# power.net
KiCad netlist of a schematic drawn in Altium Designer
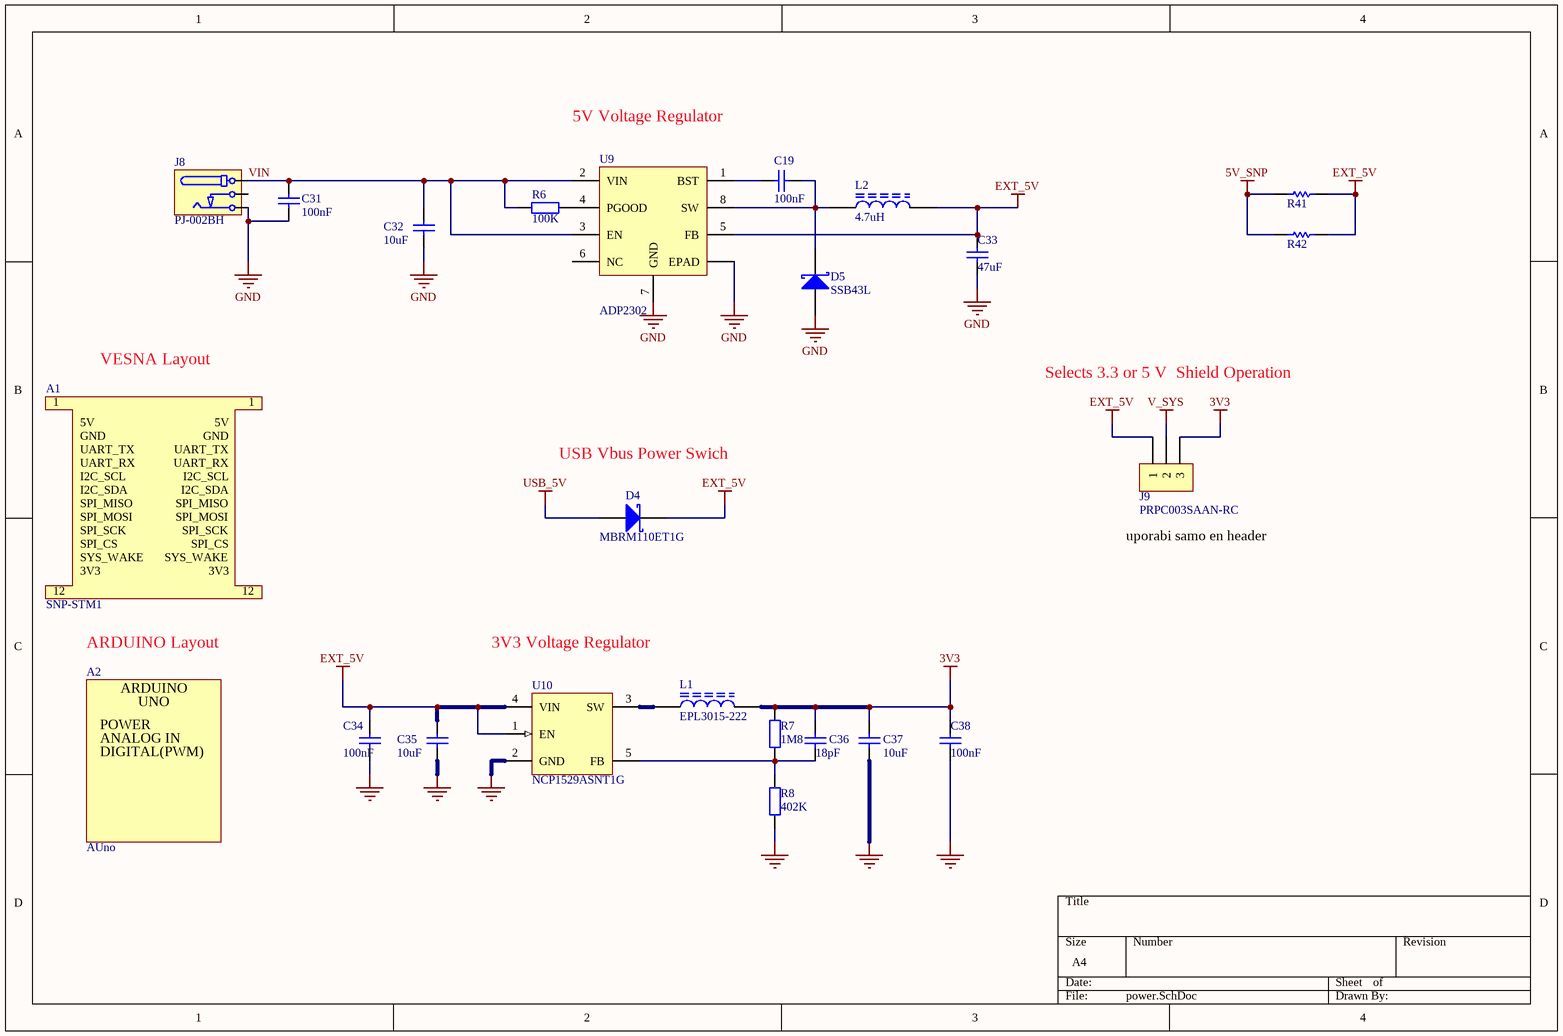
[diagram p0: power.SchDoc]

(export (version "E")
  (design (tool "Eeschema 10.0.6"))
  (components
    (comp (ref "A1")
      (value "SNP-STM1")
      (footprint "SNP-STM1")
      (description "SNP-STM1 Vesna Processor Module, Mechanical PCB Components without Connectors")
      (libsource (lib "SNP-STM1") (part "SNP-STM1"))
    )
    (comp (ref "A2") (value "AUno") (footprint "PCBComponent_1") (libsource (lib "AUNOLayout") (part "AUno")))
    (comp (ref "C19")
      (value "100nF")
      (footprint "CAPC0402(1005)60_L")
      (description "CAP 100nF 10V ±5% 0402 (1005 Metric) Thickness 0.6mm SMD")
      (fields (field (name "TOLERANCE") "Â±5%") (field (name "Comment") "CAP 100nF 10V 0402(1005)"))
      (libsource (lib "Altium Content Vault") (part "CMP-1034-02064-1"))
    )
    (comp (ref "C31")
      (value "100nF")
      (footprint "CAPC0402(1005)60_M")
      (description "CAP 100nF 50V ±10% 0402 (1005 Metric) Thickness 0.6mm SMD")
      (fields (field (name "TOLERANCE") "±10%") (field (name "Comment") "CAP 100nF 50V 0402(1005)"))
      (libsource (lib "Altium Content Vault") (part "CMP-1034-02077-1"))
    )
    (comp (ref "C32")
      (value "10uF")
      (footprint "CAPC0805(2012)145_N")
      (description "CAP 10uF 10V ±20% 0805 (2012 Metric) Thickness 1.45mm SMD")
      (fields (field (name "TOLERANCE") "±20%"))
      (libsource (lib "Altium Content Vault") (part "CMP-1036-04924-1"))
    )
    (comp (ref "C33")
      (value "47uF")
      (footprint "CAPC0402(1005)60_M")
      (description "CAP 100nF 50V ±10% 0402 (1005 Metric) Thickness 0.6mm SMD")
      (fields (field (name "TOLERANCE") "±10%") (field (name "Comment") "CAP 100nF 50V 0402(1005)"))
      (libsource (lib "Altium Content Vault") (part "CMP-1034-02077-1"))
    )
    (comp (ref "C34")
      (value "100nF")
      (footprint "CAPC0402(1005)60_M")
      (description "CAP 100nF 50V ±10% 0402 (1005 Metric) Thickness 0.6mm SMD")
      (fields (field (name "TOLERANCE") "±10%") (field (name "Comment") "CAP 100nF 50V 0402(1005)"))
      (libsource (lib "Altium Content Vault") (part "CMP-1034-02077-1"))
    )
    (comp (ref "C35")
      (value "10uF")
      (footprint "CAPC0805(2012)145_N")
      (description "CAP 10uF 10V ±20% 0805 (2012 Metric) Thickness 1.45mm SMD")
      (fields (field (name "TOLERANCE") "±20%"))
      (libsource (lib "Altium Content Vault") (part "CMP-1036-04924-1"))
    )
    (comp (ref "C36")
      (value "18pF")
      (footprint "CAPC0402(1005)60_M")
      (description "CAP 18pF 50V ±1% 0402 (1005 Metric) Thickness 0.6mm SMD")
      (fields (field (name "TOLERANCE") "±1%") (field (name "Comment") "CAP 18pF 50V 0402(1005)"))
      (libsource (lib "Altium Content Vault") (part "CMP-1034-00862-1"))
    )
    (comp (ref "C37")
      (value "10uF")
      (footprint "CAPC0805(2012)145_N")
      (description "CAP 10uF 10V ±20% 0805 (2012 Metric) Thickness 1.45mm SMD")
      (fields (field (name "TOLERANCE") "±20%"))
      (libsource (lib "Altium Content Vault") (part "CMP-1036-04924-1"))
    )
    (comp (ref "C38")
      (value "100nF")
      (footprint "CAPC0402(1005)60_M")
      (description "CAP 100nF 50V ±10% 0402 (1005 Metric) Thickness 0.6mm SMD")
      (fields (field (name "TOLERANCE") "±10%") (field (name "Comment") "CAP 100nF 50V 0402(1005)"))
      (libsource (lib "Altium Content Vault") (part "CMP-1034-02077-1"))
    )
    (comp (ref "D4")
      (value "MBRM110ET1G")
      (footprint "CASE 457–04")
      (description "Diode, Schottky Power Rectifier, SMT, 1A, 10V")
      (libsource (lib "MBRM110ET1G") (part "MBRM110ET1G"))
    )
    (comp (ref "D5")
      (value "SSB43L")
      (footprint "CASE 457–04")
      (description "Diode, Schottky Power Rectifier, SMT, 1A, 10V")
      (libsource (lib "MBRM110ET1G") (part "MBRM110ET1G"))
    )
    (comp (ref "J8") (value "PJ-002BH") (footprint "PJ-002BH") (libsource (lib "pj-002bh") (part "PJ-002BH")))
    (comp (ref "J9")
      (value "PRPC003SAAN-RC")
      (footprint "PRPC003SAAN-RC")
      (description "Pin header male 3 pin  Through Hole Vertical, Pitch 2.54 mm")
      (libsource (lib "PRPC003SAAN-RC") (part "PRPC003SAAN-RC"))
    )
    (comp (ref "L1")
      (value "EPL3015-222")
      (footprint "EPL3015-222_L")
      (description "Shielded Power Inductors, 2.2uH, Isat 1.6A @ 30%, Irms 2A @ 40°C, 3 x 3 x 1.5mm")
      (libsource (lib "EPL3015-222") (part "EPL3015-222"))
    )
    (comp (ref "L2")
      (value "4.7uH")
      (footprint "EPL3015-222_L")
      (description "Shielded Power Inductors, 4.7uH, Isat 1.6A @ 30%, Irms 1.4A @ 40°C, 3 x 3 x 1.5mm")
      (fields
        (field (name "MANUFACTURER") "COILCRAFT")
        (field (name "MANUFACTURER PART NUMBER") "EPL3015-472MLB")
      )
      (libsource (lib "EPL3015-472MLB") (part "EPL3015-472MLB"))
    )
    (comp (ref "R6")
      (value "100K")
      (footprint "RESC0402(1005)_M")
      (description "100K 0.063W 1% 0402 (1005 Metric)  SMD")
      (fields (field (name "POWER") "0.063W") (field (name "TOLERANCE") "1%"))
      (libsource (lib "RES0402(1005)") (part "100K 0402(1005)"))
    )
    (comp (ref "R7")
      (value "1M8")
      (footprint "RESC0402(1005)_L")
      (description "1M8 0.063W 1% 0402 (1005 Metric)  SMD")
      (fields (field (name "POWER") "0.063W") (field (name "TOLERANCE") "1%"))
      (libsource (lib "RES0402(1005)") (part "1M8 0402(1005)"))
    )
    (comp (ref "R8")
      (value "402K")
      (footprint "RESC0402(1005)_L")
      (description "402K 0.063W 1% 0402 (1005 Metric)  SMD")
      (fields (field (name "POWER") "0.063W") (field (name "TOLERANCE") "1%"))
      (libsource (lib "RES0402(1005)") (part "402K 0402(1005)"))
    )
    (comp (ref "R41")
      (value "Jumper 0805(2012)")
      (footprint "RESC0805(2012)_N")
      (description "Jumper 0805 (2012 Metric)")
      (fields (field (name "TOLERANCE") "None"))
      (libsource (lib "Altium Content Vault") (part "CMP-1013-00001-1"))
    )
    (comp (ref "R42")
      (value "Jumper 0805(2012)")
      (footprint "RESC0805(2012)_N")
      (description "Jumper 0805 (2012 Metric)")
      (fields (field (name "TOLERANCE") "None"))
      (libsource (lib "Altium Content Vault") (part "CMP-1013-00001-1"))
    )
    (comp (ref "U9")
      (value "ADP2302")
      (footprint "SOP127P600-8N")
      (libsource (lib "ADP2302A") (part "ADP2302"))
    )
    (comp (ref "U10")
      (value "NCP1529ASNT1G")
      (footprint "SOT-23-5_L")
      (description "1 A, 1.7 MHz Low Voltage Buck Converter")
      (libsource (lib "NCP1529") (part "NCP1529A"))
    )
  )
  (nets
    (net (code "1") (name "/VIN") (class "Default")
      (node (ref "C31") (pin "1") (pinfunction "1_1") (pintype "passive"))
      (node (ref "C32") (pin "2") (pinfunction "2_2") (pintype "passive"))
      (node (ref "J8") (pin "1") (pinfunction "S_1") (pintype "power_in"))
      (node (ref "R6") (pin "1") (pinfunction "1_1") (pintype "passive"))
      (node (ref "U9") (pin "2") (pinfunction "VIN_2") (pintype "passive"))
      (node (ref "U9") (pin "3") (pinfunction "EN_3") (pintype "passive"))
    )
    (net (code "2") (name "3V3") (class "Default")
      (node (ref "C36") (pin "2") (pinfunction "2_2") (pintype "passive"))
      (node (ref "C37") (pin "2") (pinfunction "2_2") (pintype "passive"))
      (node (ref "C38") (pin "2") (pinfunction "2_2") (pintype "passive"))
      (node (ref "J9") (pin "3") (pinfunction "3_3") (pintype "passive"))
      (node (ref "L1") (pin "2") (pinfunction "2_2") (pintype "passive"))
      (node (ref "R7") (pin "2") (pinfunction "2_2") (pintype "passive"))
    )
    (net (code "3") (name "5V_SNP") (class "Default")
      (node (ref "R41") (pin "1") (pinfunction "1_1") (pintype "passive"))
      (node (ref "R42") (pin "1") (pinfunction "1_1") (pintype "passive"))
    )
    (net (code "4") (name "EXT_5V") (class "Default")
      (node (ref "C33") (pin "2") (pinfunction "2_2") (pintype "passive"))
      (node (ref "C34") (pin "2") (pinfunction "2_2") (pintype "passive"))
      (node (ref "C35") (pin "2") (pinfunction "2_2") (pintype "passive"))
      (node (ref "D4") (pin "1") (pinfunction "K_1") (pintype "passive"))
      (node (ref "J9") (pin "1") (pinfunction "1_1") (pintype "passive"))
      (node (ref "L2") (pin "2") (pinfunction "2_2") (pintype "passive"))
      (node (ref "R41") (pin "2") (pinfunction "2_2") (pintype "passive"))
      (node (ref "R42") (pin "2") (pinfunction "2_2") (pintype "passive"))
      (node (ref "U10") (pin "1") (pinfunction "EN_1") (pintype "input"))
      (node (ref "U10") (pin "4") (pinfunction "VIN_4") (pintype "passive"))
      (node (ref "U9") (pin "5") (pinfunction "FB_5") (pintype "passive"))
    )
    (net (code "5") (name "GND") (class "Default")
      (node (ref "C31") (pin "2") (pinfunction "2_2") (pintype "passive"))
      (node (ref "C32") (pin "1") (pinfunction "1_1") (pintype "passive"))
      (node (ref "C33") (pin "1") (pinfunction "1_1") (pintype "passive"))
      (node (ref "C34") (pin "1") (pinfunction "1_1") (pintype "passive"))
      (node (ref "C35") (pin "1") (pinfunction "1_1") (pintype "passive"))
      (node (ref "C37") (pin "1") (pinfunction "1_1") (pintype "passive"))
      (node (ref "C38") (pin "1") (pinfunction "1_1") (pintype "passive"))
      (node (ref "D5") (pin "2") (pinfunction "A_2") (pintype "passive"))
      (node (ref "J8") (pin "2") (pinfunction "T_2") (pintype "power_in"))
      (node (ref "R8") (pin "1") (pinfunction "1_1") (pintype "passive"))
      (node (ref "U10") (pin "2") (pinfunction "GND_2") (pintype "power_in"))
      (node (ref "U9") (pin "7") (pinfunction "GND_7") (pintype "passive"))
      (node (ref "U9") (pin "9") (pinfunction "EPAD_9") (pintype "passive"))
    )
    (net (code "6") (name "Net-(D5-K)") (class "Default")
      (node (ref "C19") (pin "2") (pinfunction "2_2") (pintype "passive"))
      (node (ref "D5") (pin "1") (pinfunction "K_1") (pintype "passive"))
      (node (ref "L2") (pin "1") (pinfunction "1_1") (pintype "passive"))
      (node (ref "U9") (pin "8") (pinfunction "SW_8") (pintype "passive"))
    )
    (net (code "7") (name "Net-(U9-BST)") (class "Default")
      (node (ref "C19") (pin "1") (pinfunction "1_1") (pintype "passive"))
      (node (ref "U9") (pin "1") (pinfunction "BST_1") (pintype "passive"))
    )
    (net (code "8") (name "Net-(U9-PGOOD)") (class "Default")
      (node (ref "R6") (pin "2") (pinfunction "2_2") (pintype "passive"))
      (node (ref "U9") (pin "4") (pinfunction "PGOOD_4") (pintype "passive"))
    )
    (net (code "9") (name "Net-(U10-FB)") (class "Default")
      (node (ref "C36") (pin "1") (pinfunction "1_1") (pintype "passive"))
      (node (ref "R7") (pin "1") (pinfunction "1_1") (pintype "passive"))
      (node (ref "R8") (pin "2") (pinfunction "2_2") (pintype "passive"))
      (node (ref "U10") (pin "5") (pinfunction "FB_5") (pintype "passive"))
    )
    (net (code "10") (name "Net-(U10-SW)") (class "Default")
      (node (ref "L1") (pin "1") (pinfunction "1_1") (pintype "passive"))
      (node (ref "U10") (pin "3") (pinfunction "SW_3") (pintype "passive"))
    )
    (net (code "11") (name "USB_5V") (class "Default")
      (node (ref "D4") (pin "2") (pinfunction "A_2") (pintype "passive"))
    )
    (net (code "12") (name "V_SYS") (class "Default")
      (node (ref "J9") (pin "2") (pinfunction "2_2") (pintype "passive"))
    )
    (net (code "13") (name "unconnected-(J8-R-Pad3)") (class "Default")
      (node (ref "J8") (pin "3") (pinfunction "R_3") (pintype "power_in"))
    )
    (net (code "14") (name "unconnected-(U9-NC-Pad6)") (class "Default")
      (node (ref "U9") (pin "6") (pinfunction "NC_6") (pintype "passive"))
    )
  )
)
